# Snowman.net
KiCad netlist of a schematic drawn in EAGLE
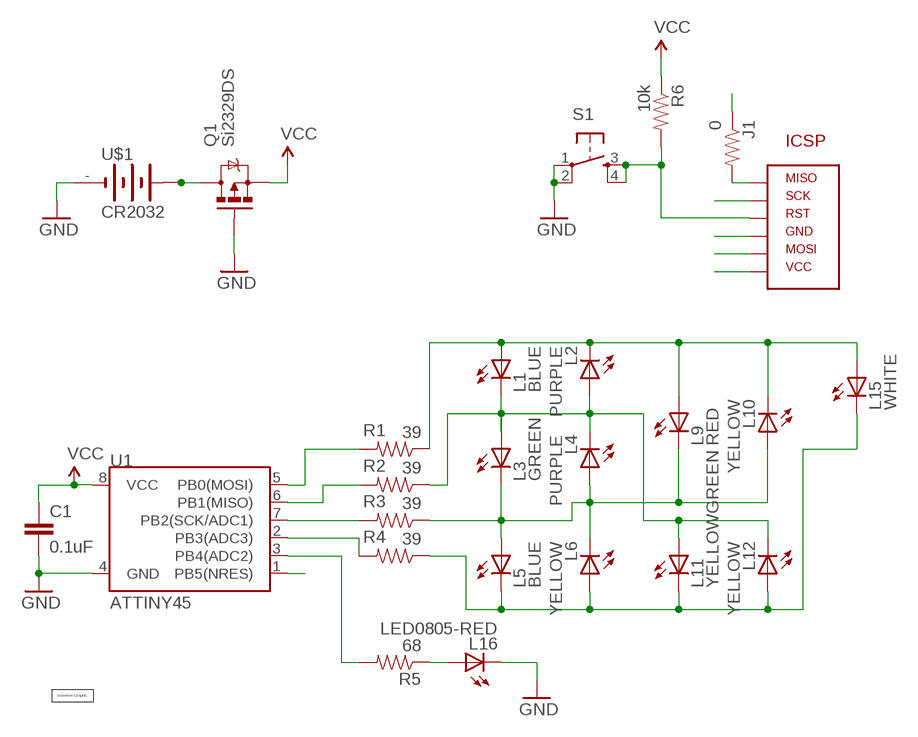
[diagram p0: schematic, sheet 1]

(export (version "E")
  (design (tool "Eeschema 10.0.6"))
  (components
    (comp (ref "C1")
      (value "0.1uF")
      (footprint "eagle-import:0805")
      (libsource (lib "eagle-import") (part "CAP0805"))
    )
    (comp (ref "J1")
      (value "0")
      (footprint "eagle-import:0805")
      (libsource (lib "eagle-import") (part "RESISTOR0805-RES"))
    )
    (comp (ref "L1")
      (value "BLUE")
      (footprint "eagle-import:LED-0805-RED")
      (libsource (lib "eagle-import") (part "LED0805-RED"))
    )
    (comp (ref "L2")
      (value "PURPLE")
      (footprint "eagle-import:LED-0805-GREEN")
      (libsource (lib "eagle-import") (part "LED0805-GREEN"))
    )
    (comp (ref "L3")
      (value "GREEN")
      (footprint "eagle-import:LED-0805-RED")
      (libsource (lib "eagle-import") (part "LED0805-RED"))
    )
    (comp (ref "L4")
      (value "PURPLE")
      (footprint "eagle-import:LED-0805-GREEN")
      (libsource (lib "eagle-import") (part "LED0805-GREEN"))
    )
    (comp (ref "L5")
      (value "BLUE")
      (footprint "eagle-import:LED-0805-RED")
      (libsource (lib "eagle-import") (part "LED0805-RED"))
    )
    (comp (ref "L6")
      (value "YELLOW")
      (footprint "eagle-import:LED-0805-GREEN")
      (libsource (lib "eagle-import") (part "LED0805-GREEN"))
    )
    (comp (ref "L9")
      (value "RED")
      (footprint "eagle-import:LED-0805-RED")
      (libsource (lib "eagle-import") (part "LED0805-RED"))
    )
    (comp (ref "L10")
      (value "YELLOW")
      (footprint "eagle-import:LED-0805-GREEN")
      (libsource (lib "eagle-import") (part "LED0805-GREEN"))
    )
    (comp (ref "L11")
      (value "YELLOWGREEN")
      (footprint "eagle-import:LED-0805-GREEN")
      (libsource (lib "eagle-import") (part "LED0805-GREEN"))
    )
    (comp (ref "L12")
      (value "YELLOW")
      (footprint "eagle-import:LED-0805-RED")
      (libsource (lib "eagle-import") (part "LED0805-RED"))
    )
    (comp (ref "L15")
      (value "WHITE")
      (footprint "eagle-import:LED-0805-RED")
      (libsource (lib "eagle-import") (part "LED0805-RED"))
    )
    (comp (ref "L16")
      (value "LED0805-RED")
      (footprint "eagle-import:LED-0805-RED")
      (libsource (lib "eagle-import") (part "LED0805-RED"))
    )
    (comp (ref "Q1")
      (value "Si2329DS")
      (footprint "eagle-import:SOT23-3")
      (libsource (lib "eagle-import") (part "MOSFET_P_CH"))
    )
    (comp (ref "R1")
      (value "39")
      (footprint "eagle-import:0805")
      (libsource (lib "eagle-import") (part "SparkFun-Resistors_RESISTOR0805-RES"))
    )
    (comp (ref "R2")
      (value "39")
      (footprint "eagle-import:0805")
      (libsource (lib "eagle-import") (part "SparkFun-Resistors_RESISTOR0805-RES"))
    )
    (comp (ref "R3")
      (value "39")
      (footprint "eagle-import:0805")
      (libsource (lib "eagle-import") (part "SparkFun-Resistors_RESISTOR0805-RES"))
    )
    (comp (ref "R4")
      (value "39")
      (footprint "eagle-import:0805")
      (libsource (lib "eagle-import") (part "SparkFun-Resistors_RESISTOR0805-RES"))
    )
    (comp (ref "R5")
      (value "68")
      (footprint "eagle-import:0805")
      (libsource (lib "eagle-import") (part "SparkFun-Resistors_RESISTOR0805-RES"))
    )
    (comp (ref "R6")
      (value "10k")
      (footprint "eagle-import:0805")
      (libsource (lib "eagle-import") (part "SparkFun-Resistors_RESISTOR0805-RES"))
    )
    (comp (ref "S1")
      (value "TAC_SWITCHSMD")
      (footprint "eagle-import:TACTILE_SWITCH_SMD")
      (libsource (lib "eagle-import") (part "TAC_SWITCHSMD"))
    )
    (comp (ref "U$1")
      (value "CR2032")
      (footprint "eagle-import:BAT-HLD-001")
      (libsource (lib "eagle-import") (part "BAT-HLD-001"))
    )
    (comp (ref "U$2")
      (value "5X6_SNOWMAN5X5")
      (footprint "eagle-import:5X5_SNOWMAN")
      (libsource (lib "eagle-import") (part "5X6_SNOWMAN5X5"))
    )
    (comp (ref "U$3")
      (value "AVR_ICSP_6P6PIN")
      (footprint "eagle-import:AVR_ICSP_6P_SMD")
      (libsource (lib "eagle-import") (part "AVR_ICSP_6P6PIN"))
    )
    (comp (ref "U1")
      (value "ATTINY45")
      (footprint "eagle-import:SO08-EIAJ")
      (libsource (lib "eagle-import") (part "ATTINY45"))
    )
  )
  (nets
    (net (code "1") (name "/MISO") (class "Default")
      (node (ref "J1") (pin "1") (pinfunction "1_1") (pintype "passive"))
      (node (ref "R2") (pin "2") (pinfunction "2_2") (pintype "passive"))
      (node (ref "U1") (pin "6") (pinfunction "PB1(MISO)_6") (pintype "bidirectional"))
    )
    (net (code "2") (name "/MOSI") (class "Default")
      (node (ref "R1") (pin "2") (pinfunction "2_2") (pintype "passive"))
      (node (ref "U$3") (pin "MOSI") (pinfunction "P$5_MOSI") (pintype "bidirectional"))
      (node (ref "U1") (pin "5") (pinfunction "PB0(MOSI)_5") (pintype "bidirectional"))
    )
    (net (code "3") (name "/RST") (class "Default")
      (node (ref "R6") (pin "2") (pinfunction "2_2") (pintype "passive"))
      (node (ref "S1") (pin "3") (pinfunction "3_3") (pintype "passive"))
      (node (ref "S1") (pin "4") (pinfunction "4_4") (pintype "passive"))
      (node (ref "U$3") (pin "RST") (pinfunction "P$3_RST") (pintype "bidirectional"))
      (node (ref "U1") (pin "1") (pinfunction "PB5(NRES)_1") (pintype "bidirectional"))
    )
    (net (code "4") (name "/SCK") (class "Default")
      (node (ref "R3") (pin "2") (pinfunction "2_2") (pintype "passive"))
      (node (ref "U$3") (pin "SCK") (pinfunction "P$2_SCK") (pintype "bidirectional"))
      (node (ref "U1") (pin "7") (pinfunction "PB2(SCK/ADC1)_7") (pintype "bidirectional"))
    )
    (net (code "5") (name "GND") (class "Default")
      (node (ref "C1") (pin "2") (pinfunction "2_2") (pintype "passive"))
      (node (ref "L16") (pin "C") (pinfunction "C_C") (pintype "passive"))
      (node (ref "Q1") (pin "1") (pinfunction "G_1") (pintype "passive"))
      (node (ref "S1") (pin "1") (pinfunction "1_1") (pintype "passive"))
      (node (ref "S1") (pin "2") (pinfunction "2_2") (pintype "passive"))
      (node (ref "U$1") (pin "-") (pinfunction "-_-") (pintype "passive"))
      (node (ref "U$3") (pin "GND") (pinfunction "P$4_GND") (pintype "bidirectional"))
      (node (ref "U1") (pin "4") (pinfunction "GND_4") (pintype "bidirectional"))
    )
    (net (code "6") (name "Net-(L1-PadA)") (class "Default")
      (node (ref "L1") (pin "A") (pinfunction "A_A") (pintype "passive"))
      (node (ref "L10") (pin "C") (pinfunction "C_C") (pintype "passive"))
      (node (ref "L15") (pin "A") (pinfunction "A_A") (pintype "passive"))
      (node (ref "L2") (pin "C") (pinfunction "C_C") (pintype "passive"))
      (node (ref "L9") (pin "A") (pinfunction "A_A") (pintype "passive"))
      (node (ref "R1") (pin "1") (pinfunction "1_1") (pintype "passive"))
    )
    (net (code "7") (name "Net-(L1-PadC)") (class "Default")
      (node (ref "L1") (pin "C") (pinfunction "C_C") (pintype "passive"))
      (node (ref "L11") (pin "A") (pinfunction "A_A") (pintype "passive"))
      (node (ref "L12") (pin "C") (pinfunction "C_C") (pintype "passive"))
      (node (ref "L2") (pin "A") (pinfunction "A_A") (pintype "passive"))
      (node (ref "L3") (pin "A") (pinfunction "A_A") (pintype "passive"))
      (node (ref "L4") (pin "C") (pinfunction "C_C") (pintype "passive"))
      (node (ref "R2") (pin "1") (pinfunction "1_1") (pintype "passive"))
    )
    (net (code "8") (name "Net-(L10-PadA)") (class "Default")
      (node (ref "L10") (pin "A") (pinfunction "A_A") (pintype "passive"))
      (node (ref "L3") (pin "C") (pinfunction "C_C") (pintype "passive"))
      (node (ref "L4") (pin "A") (pinfunction "A_A") (pintype "passive"))
      (node (ref "L5") (pin "A") (pinfunction "A_A") (pintype "passive"))
      (node (ref "L6") (pin "C") (pinfunction "C_C") (pintype "passive"))
      (node (ref "L9") (pin "C") (pinfunction "C_C") (pintype "passive"))
      (node (ref "R3") (pin "1") (pinfunction "1_1") (pintype "passive"))
    )
    (net (code "9") (name "Net-(L11-PadC)") (class "Default")
      (node (ref "L11") (pin "C") (pinfunction "C_C") (pintype "passive"))
      (node (ref "L12") (pin "A") (pinfunction "A_A") (pintype "passive"))
      (node (ref "L15") (pin "C") (pinfunction "C_C") (pintype "passive"))
      (node (ref "L5") (pin "C") (pinfunction "C_C") (pintype "passive"))
      (node (ref "L6") (pin "A") (pinfunction "A_A") (pintype "passive"))
      (node (ref "R4") (pin "1") (pinfunction "1_1") (pintype "passive"))
    )
    (net (code "10") (name "Net-(L16-PadA)") (class "Default")
      (node (ref "L16") (pin "A") (pinfunction "A_A") (pintype "passive"))
      (node (ref "R5") (pin "1") (pinfunction "1_1") (pintype "passive"))
    )
    (net (code "11") (name "Net-(Q1-D)") (class "Default")
      (node (ref "Q1") (pin "3") (pinfunction "D_3") (pintype "passive"))
      (node (ref "U$1") (pin "+@1") (pinfunction "+_+@1") (pintype "passive"))
      (node (ref "U$1") (pin "+@2") (pinfunction "+_+@2") (pintype "passive"))
    )
    (net (code "12") (name "Net-(U$3-P$1)") (class "Default")
      (node (ref "J1") (pin "2") (pinfunction "2_2") (pintype "passive"))
      (node (ref "U$3") (pin "MISO") (pinfunction "P$1_MISO") (pintype "bidirectional"))
    )
    (net (code "13") (name "Net-(U1-PB3(ADC3))") (class "Default")
      (node (ref "R4") (pin "2") (pinfunction "2_2") (pintype "passive"))
      (node (ref "U1") (pin "2") (pinfunction "PB3(ADC3)_2") (pintype "bidirectional"))
    )
    (net (code "14") (name "Net-(U1-PB4(ADC2))") (class "Default")
      (node (ref "R5") (pin "2") (pinfunction "2_2") (pintype "passive"))
      (node (ref "U1") (pin "3") (pinfunction "PB4(ADC2)_3") (pintype "bidirectional"))
    )
    (net (code "15") (name "VCC") (class "Default")
      (node (ref "C1") (pin "1") (pinfunction "1_1") (pintype "passive"))
      (node (ref "Q1") (pin "2") (pinfunction "S_2") (pintype "passive"))
      (node (ref "R6") (pin "1") (pinfunction "1_1") (pintype "passive"))
      (node (ref "U$3") (pin "VCC") (pinfunction "P$6_VCC") (pintype "bidirectional"))
      (node (ref "U1") (pin "8") (pinfunction "VCC_8") (pintype "bidirectional"))
    )
  )
)
